# output_stage_and_VCA_v2.net
KiCad netlist of a schematic drawn in EAGLE
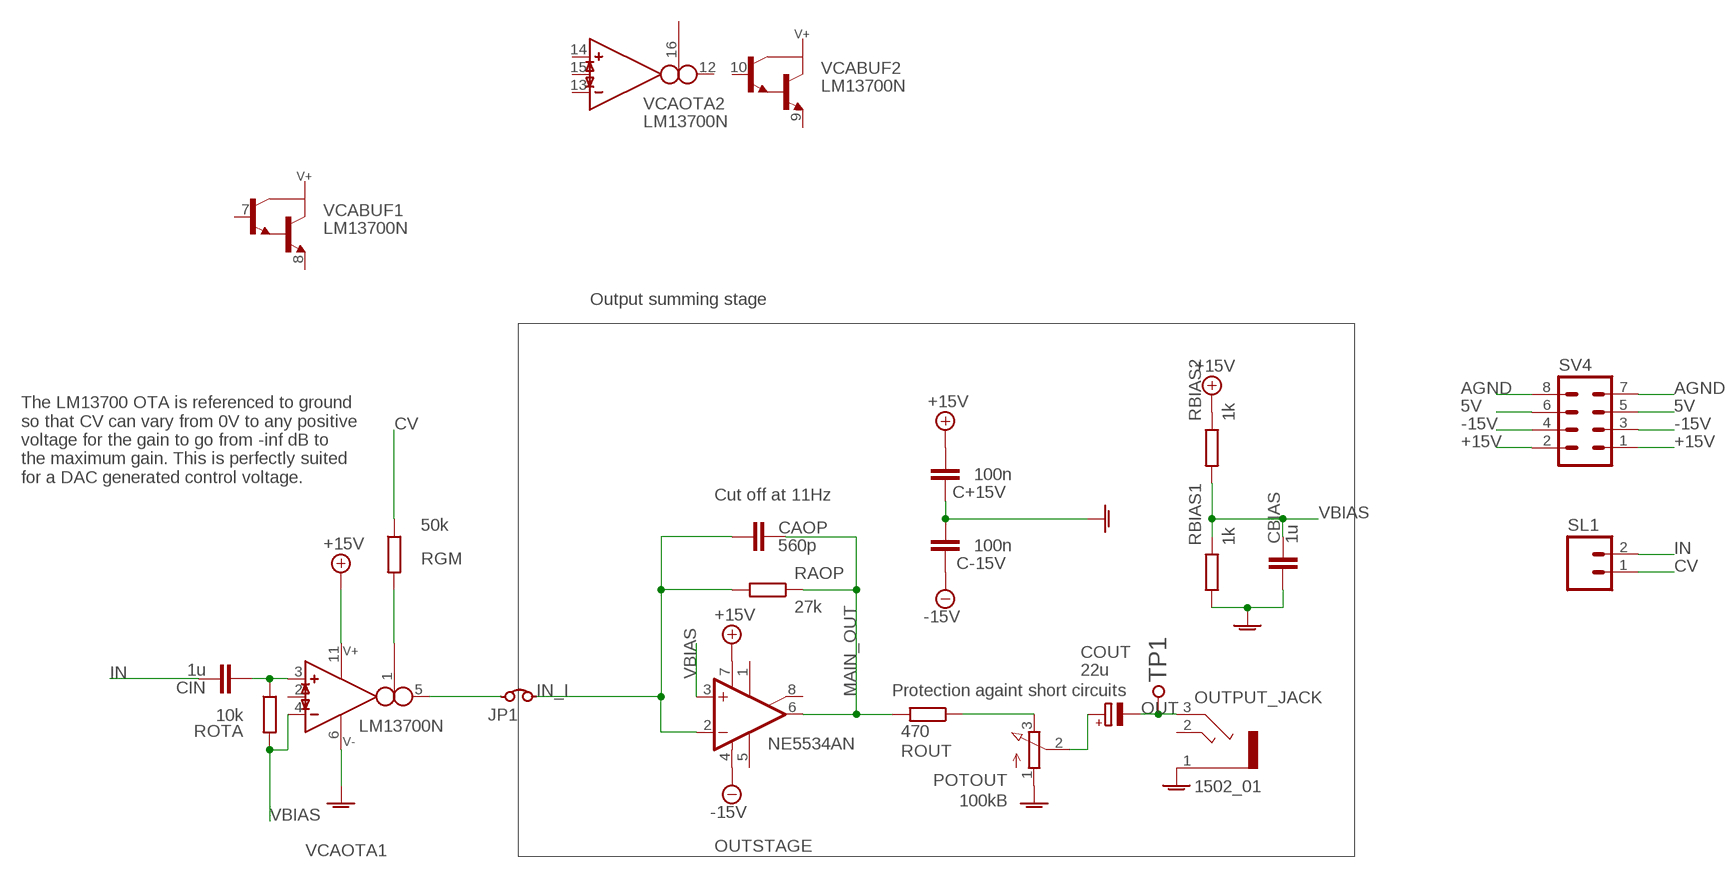
[diagram p0: schematic, sheet 1]

(export (version "E")
  (design (tool "Eeschema 10.0.6"))
  (components
    (comp (ref "C+15V")
      (value "100n")
      (footprint "eagle-import:C050-030X075")
      (libsource (lib "eagle-import") (part "C-EU050-030X075"))
    )
    (comp (ref "C-15V")
      (value "100n")
      (footprint "eagle-import:C050-030X075")
      (libsource (lib "eagle-import") (part "C-EU050-030X075"))
    )
    (comp (ref "CAOP")
      (value "560p")
      (footprint "eagle-import:C050-030X075")
      (libsource (lib "eagle-import") (part "C-EU050-030X075"))
    )
    (comp (ref "CBIAS")
      (value "1u")
      (footprint "eagle-import:C050-030X075")
      (libsource (lib "eagle-import") (part "C-EU050-030X075"))
    )
    (comp (ref "CIN")
      (value "1u")
      (footprint "eagle-import:C050-030X075")
      (libsource (lib "eagle-import") (part "C-EU050-030X075"))
    )
    (comp (ref "COUT")
      (value "22u")
      (footprint "eagle-import:B45181B")
      (libsource (lib "eagle-import") (part "CPOL-EUB45181B"))
    )
    (comp (ref "JP1")
      (value "JUMPER")
      (footprint "eagle-import:HDR2X1")
      (libsource (lib "eagle-import") (part "JUMPER"))
    )
    (comp (ref "OUTPUT_JACK")
      (value "1502_01")
      (footprint "eagle-import:1502_01")
      (libsource (lib "eagle-import") (part "1502_01"))
    )
    (comp (ref "OUTSTAGE")
      (value "NE5534AN")
      (footprint "eagle-import:DIL08")
      (libsource (lib "eagle-import") (part "NE5534NA"))
    )
    (comp (ref "POTOUT")
      (value "100kB")
      (footprint "eagle-import:3RP_1610N")
      (libsource (lib "eagle-import") (part "3RP/1610N"))
    )
    (comp (ref "RAOP")
      (value "27k")
      (footprint "eagle-import:0204_7")
      (libsource (lib "eagle-import") (part "R-EU_0204/7"))
    )
    (comp (ref "RBIAS1")
      (value "1k")
      (footprint "eagle-import:0204_7")
      (libsource (lib "eagle-import") (part "R-EU_0204/7"))
    )
    (comp (ref "RBIAS2")
      (value "1k")
      (footprint "eagle-import:0204_7")
      (libsource (lib "eagle-import") (part "R-EU_0204/7"))
    )
    (comp (ref "RGM")
      (value "50k")
      (footprint "eagle-import:0204_7")
      (libsource (lib "eagle-import") (part "R-EU_0204/7"))
    )
    (comp (ref "ROTA")
      (value "10k")
      (footprint "eagle-import:0204_7")
      (libsource (lib "eagle-import") (part "R-EU_0204/7"))
    )
    (comp (ref "ROUT")
      (value "470")
      (footprint "eagle-import:0204_7")
      (libsource (lib "eagle-import") (part "R-EU_0204/7"))
    )
    (comp (ref "SL1")
      (value "MA02")
      (footprint "eagle-import:02PA")
      (libsource (lib "eagle-import") (part "MA02"))
    )
    (comp (ref "SV4")
      (value "MA04-2")
      (footprint "eagle-import:MA04-2")
      (libsource (lib "eagle-import") (part "MA04-2"))
    )
    (comp (ref "TP1")
      (value "TESTPOINT")
      (footprint "eagle-import:TESTPOINT_63")
      (libsource (lib "eagle-import") (part "TESTPOINT"))
    )
    (comp (ref "VCA")
      (value "LM13700N")
      (footprint "eagle-import:DIL16")
      (libsource (lib "eagle-import") (part "LM13700N"))
    )
  )
  (nets
    (net (code "1") (name "+15V") (class "Default")
      (node (ref "C+15V") (pin "2") (pinfunction "2_2") (pintype "passive"))
      (node (ref "OUTSTAGE") (pin "7") (pinfunction "V+_7") (pintype "power_in"))
      (node (ref "RBIAS2") (pin "1") (pinfunction "1_1") (pintype "passive"))
      (node (ref "SV4") (pin "1") (pinfunction "1_1") (pintype "passive"))
      (node (ref "SV4") (pin "2") (pinfunction "2_2") (pintype "passive"))
      (node (ref "VCA") (pin "11") (pinfunction "V+_11") (pintype "power_in"))
    )
    (net (code "2") (name "-15V") (class "Default")
      (node (ref "C-15V") (pin "1") (pinfunction "1_1") (pintype "passive"))
      (node (ref "OUTSTAGE") (pin "4") (pinfunction "V-_4") (pintype "power_in"))
      (node (ref "SV4") (pin "3") (pinfunction "3_3") (pintype "passive"))
      (node (ref "SV4") (pin "4") (pinfunction "4_4") (pintype "passive"))
    )
    (net (code "3") (name "/5V") (class "Default")
      (node (ref "SV4") (pin "5") (pinfunction "5_5") (pintype "passive"))
      (node (ref "SV4") (pin "6") (pinfunction "6_6") (pintype "passive"))
    )
    (net (code "4") (name "/CV") (class "Default")
      (node (ref "RGM") (pin "1") (pinfunction "1_1") (pintype "passive"))
      (node (ref "SL1") (pin "1") (pinfunction "1_1") (pintype "passive"))
    )
    (net (code "5") (name "/IN") (class "Default")
      (node (ref "CIN") (pin "1") (pinfunction "1_1") (pintype "passive"))
      (node (ref "SL1") (pin "2") (pinfunction "2_2") (pintype "passive"))
    )
    (net (code "6") (name "/IN_I") (class "Default")
      (node (ref "CAOP") (pin "2") (pinfunction "2_2") (pintype "passive"))
      (node (ref "JP1") (pin "2") (pinfunction "2_2") (pintype "passive"))
      (node (ref "OUTSTAGE") (pin "2") (pinfunction "-IN_2") (pintype "input"))
      (node (ref "RAOP") (pin "2") (pinfunction "2_2") (pintype "passive"))
    )
    (net (code "7") (name "/MAIN_OUT") (class "Default")
      (node (ref "CAOP") (pin "1") (pinfunction "1_1") (pintype "passive"))
      (node (ref "OUTSTAGE") (pin "6") (pinfunction "OUT_6") (pintype "output"))
      (node (ref "RAOP") (pin "1") (pinfunction "1_1") (pintype "passive"))
      (node (ref "ROUT") (pin "2") (pinfunction "2_2") (pintype "passive"))
    )
    (net (code "8") (name "/OUT") (class "Default")
      (node (ref "COUT") (pin "-") (pinfunction "-_-") (pintype "passive"))
      (node (ref "OUTPUT_JACK") (pin "3") (pinfunction "2_3") (pintype "passive"))
      (node (ref "TP1") (pin "P$1") (pinfunction "P$1_P$1") (pintype "passive"))
    )
    (net (code "9") (name "/VBIAS") (class "Default")
      (node (ref "CBIAS") (pin "1") (pinfunction "1_1") (pintype "passive"))
      (node (ref "OUTSTAGE") (pin "3") (pinfunction "+IN_3") (pintype "input"))
      (node (ref "RBIAS1") (pin "1") (pinfunction "1_1") (pintype "passive"))
      (node (ref "RBIAS2") (pin "2") (pinfunction "2_2") (pintype "passive"))
      (node (ref "ROTA") (pin "2") (pinfunction "2_2") (pintype "passive"))
      (node (ref "VCA") (pin "4") (pinfunction "IN_N_4") (pintype "input"))
    )
    (net (code "10") (name "AGND") (class "Default")
      (node (ref "C+15V") (pin "1") (pinfunction "1_1") (pintype "passive"))
      (node (ref "C-15V") (pin "2") (pinfunction "2_2") (pintype "passive"))
      (node (ref "CBIAS") (pin "2") (pinfunction "2_2") (pintype "passive"))
      (node (ref "OUTPUT_JACK") (pin "1") (pinfunction "1_1") (pintype "passive"))
      (node (ref "POTOUT") (pin "1") (pinfunction "A_1") (pintype "passive"))
      (node (ref "RBIAS1") (pin "2") (pinfunction "2_2") (pintype "passive"))
      (node (ref "SV4") (pin "7") (pinfunction "7_7") (pintype "passive"))
      (node (ref "SV4") (pin "8") (pinfunction "8_8") (pintype "passive"))
      (node (ref "VCA") (pin "6") (pinfunction "V-_6") (pintype "power_in"))
    )
    (net (code "11") (name "Net-(POTOUT-E)") (class "Default")
      (node (ref "POTOUT") (pin "3") (pinfunction "E_3") (pintype "passive"))
      (node (ref "ROUT") (pin "1") (pinfunction "1_1") (pintype "passive"))
    )
    (net (code "12") (name "Net-(POTOUT-S)") (class "Default")
      (node (ref "COUT") (pin "+") (pinfunction "+_+") (pintype "passive"))
      (node (ref "POTOUT") (pin "2") (pinfunction "S_2") (pintype "passive"))
    )
    (net (code "13") (name "Net-(VCAC-IN_P)") (class "Default")
      (node (ref "CIN") (pin "2") (pinfunction "2_2") (pintype "passive"))
      (node (ref "ROTA") (pin "1") (pinfunction "1_1") (pintype "passive"))
      (node (ref "VCA") (pin "3") (pinfunction "IN_P_3") (pintype "input"))
    )
    (net (code "14") (name "Net-(VCAC-I_BIAS)") (class "Default")
      (node (ref "RGM") (pin "2") (pinfunction "2_2") (pintype "passive"))
      (node (ref "VCA") (pin "1") (pinfunction "I_BIAS_1") (pintype "input"))
    )
    (net (code "15") (name "Net-(VCAC-OUT)") (class "Default")
      (node (ref "JP1") (pin "1") (pinfunction "1_1") (pintype "passive"))
      (node (ref "VCA") (pin "5") (pinfunction "OUT_5") (pintype "output"))
    )
    (net (code "16") (name "unconnected-(OUTPUT_JACK-3-Pad2)") (class "Default")
      (node (ref "OUTPUT_JACK") (pin "2") (pinfunction "3_2") (pintype "passive"))
    )
    (net (code "17") (name "unconnected-(OUTSTAGE-CMP-Pad5)") (class "Default")
      (node (ref "OUTSTAGE") (pin "5") (pinfunction "CMP_5") (pintype "passive"))
    )
    (net (code "18") (name "unconnected-(OUTSTAGE-ON-Pad1)") (class "Default")
      (node (ref "OUTSTAGE") (pin "1") (pinfunction "ON_1") (pintype "passive"))
    )
    (net (code "19") (name "unconnected-(OUTSTAGE-ON{slash}CMP-Pad8)") (class "Default")
      (node (ref "OUTSTAGE") (pin "8") (pinfunction "ON/CMP_8") (pintype "passive"))
    )
    (net (code "20") (name "unconnected-(VCAA-B-Pad7)") (class "Default")
      (node (ref "VCA") (pin "7") (pinfunction "B_7") (pintype "passive"))
    )
    (net (code "21") (name "unconnected-(VCAA-E-Pad8)") (class "Default")
      (node (ref "VCA") (pin "8") (pinfunction "E_8") (pintype "passive"))
    )
    (net (code "22") (name "unconnected-(VCAB-B-Pad10)") (class "Default")
      (node (ref "VCA") (pin "10") (pinfunction "B_10") (pintype "passive"))
    )
    (net (code "23") (name "unconnected-(VCAB-E-Pad9)") (class "Default")
      (node (ref "VCA") (pin "9") (pinfunction "E_9") (pintype "passive"))
    )
    (net (code "24") (name "unconnected-(VCAC-I_DIODE-Pad2)") (class "Default")
      (node (ref "VCA") (pin "2") (pinfunction "I_DIODE_2") (pintype "input"))
    )
    (net (code "25") (name "unconnected-(VCAD-IN_N-Pad13)") (class "Default")
      (node (ref "VCA") (pin "13") (pinfunction "IN_N_13") (pintype "input"))
    )
    (net (code "26") (name "unconnected-(VCAD-IN_P-Pad14)") (class "Default")
      (node (ref "VCA") (pin "14") (pinfunction "IN_P_14") (pintype "input"))
    )
    (net (code "27") (name "unconnected-(VCAD-I_BIAS-Pad16)") (class "Default")
      (node (ref "VCA") (pin "16") (pinfunction "I_BIAS_16") (pintype "input"))
    )
    (net (code "28") (name "unconnected-(VCAD-I_DIODE-Pad15)") (class "Default")
      (node (ref "VCA") (pin "15") (pinfunction "I_DIODE_15") (pintype "input"))
    )
    (net (code "29") (name "unconnected-(VCAD-OUT-Pad12)") (class "Default")
      (node (ref "VCA") (pin "12") (pinfunction "OUT_12") (pintype "output"))
    )
  )
)
